# Telemetry_AnalogSensors_PTC08_Shifter.net
KiCad netlist of a schematic drawn in Altium Designer
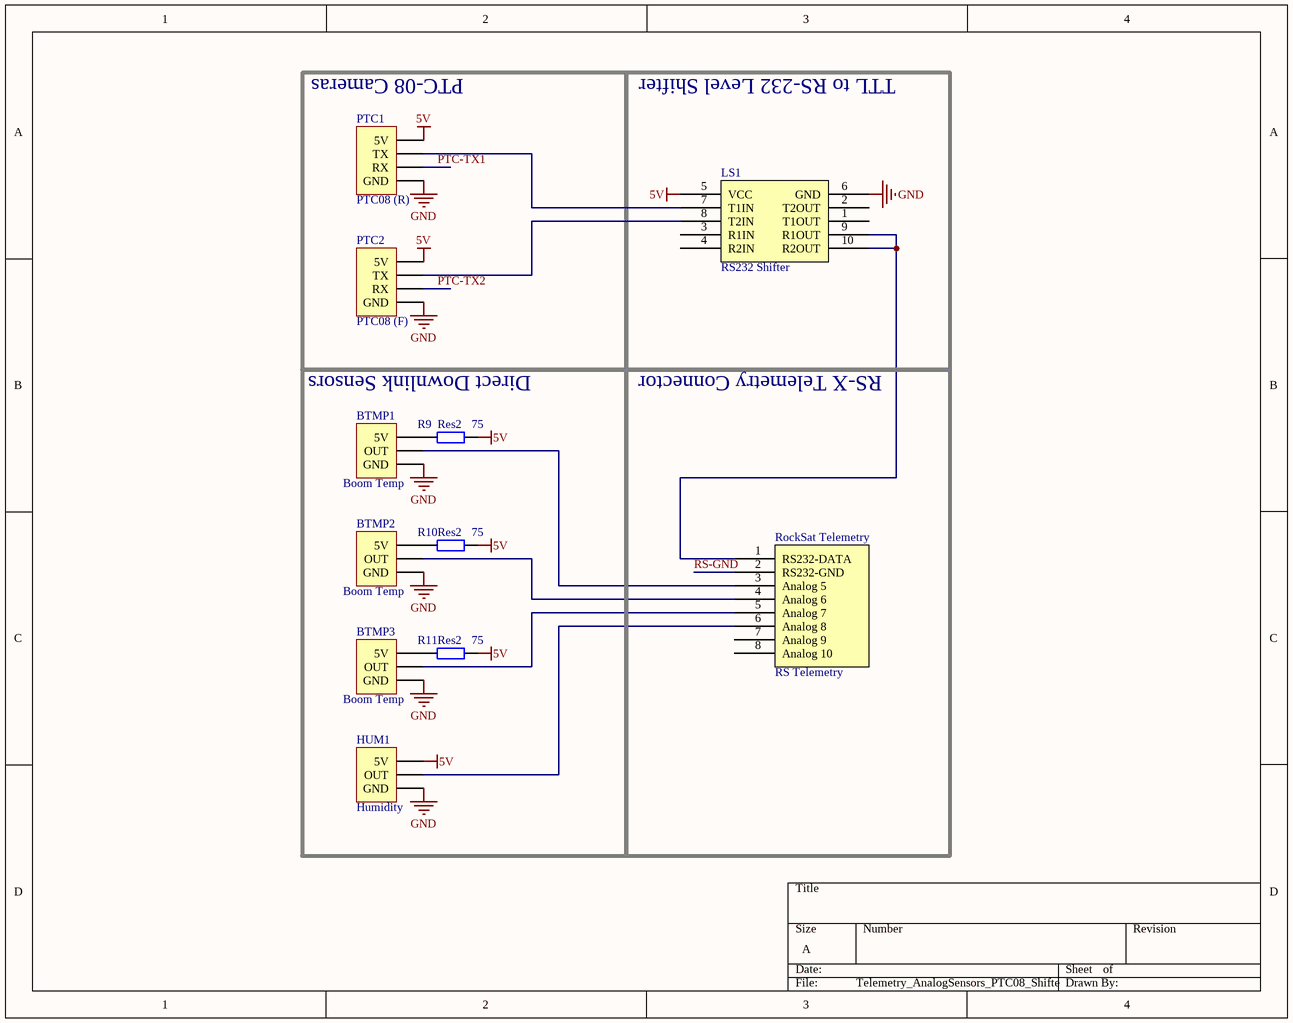
[diagram p0: Telemetry_AnalogSensors_PTC08_Shifter.SchDoc]

(export (version "E")
  (design (tool "Eeschema 10.0.6"))
  (components
    (comp (ref "BTMP1")
      (value "Boom Temp")
      (footprint "HDR1X3")
      (description "Header, 3-Pin")
      (fields (field (name "PUBLISHER") "Altium Limited"))
      (libsource (lib "Miscellaneous Connectors") (part "Header 3"))
    )
    (comp (ref "BTMP2")
      (value "Boom Temp")
      (footprint "HDR1X3")
      (description "Header, 3-Pin")
      (fields (field (name "PUBLISHER") "Altium Limited"))
      (libsource (lib "Miscellaneous Connectors") (part "Header 3"))
    )
    (comp (ref "BTMP3")
      (value "Boom Temp")
      (footprint "HDR1X3")
      (description "Header, 3-Pin")
      (fields (field (name "PUBLISHER") "Altium Limited"))
      (libsource (lib "Miscellaneous Connectors") (part "Header 3"))
    )
    (comp (ref "HUM1")
      (value "Humidity")
      (footprint "HDR1X3")
      (description "Header, 3-Pin")
      (fields (field (name "PUBLISHER") "Altium Limited"))
      (libsource (lib "Miscellaneous Connectors") (part "Header 3"))
    )
    (comp (ref "LS1") (value "RS232 Shifter") (libsource (lib "MAX3232") (part "Component_1")))
    (comp (ref "PTC1")
      (value "PTC08 (R)")
      (footprint "HDR1X4")
      (description "Header, 4-Pin")
      (fields (field (name "PUBLISHER") "Altium Limited"))
      (libsource (lib "Miscellaneous Connectors") (part "Header 4"))
    )
    (comp (ref "PTC2")
      (value "PTC08 (F)")
      (footprint "HDR1X4")
      (description "Header, 4-Pin")
      (fields (field (name "PUBLISHER") "Altium Limited"))
      (libsource (lib "Miscellaneous Connectors") (part "Header 4"))
    )
    (comp (ref "R9")
      (value "Res2")
      (footprint "AXIAL-0.4")
      (description "Resistor")
      (fields (field (name "ALTIUM_VALUE") "75") (field (name "PUBLISHER") "Altium Limited"))
      (libsource (lib "Miscellaneous Devices") (part "Res2"))
    )
    (comp (ref "R10")
      (value "Res2")
      (footprint "AXIAL-0.4")
      (description "Resistor")
      (fields (field (name "ALTIUM_VALUE") "75") (field (name "PUBLISHER") "Altium Limited"))
      (libsource (lib "Miscellaneous Devices") (part "Res2"))
    )
    (comp (ref "R11")
      (value "Res2")
      (footprint "AXIAL-0.4")
      (description "Resistor")
      (fields (field (name "ALTIUM_VALUE") "75") (field (name "PUBLISHER") "Altium Limited"))
      (libsource (lib "Miscellaneous Devices") (part "Res2"))
    )
    (comp (ref "RockSat Telemetry")
      (value "RS Telemetry")
      (libsource (lib "RSX_Telemetry") (part "Component_1"))
    )
  )
  (nets
    (net (code "1") (name "/PTC-TX1") (class "Default")
      (node (ref "PTC1") (pin "3") (pinfunction "RX_3") (pintype "passive"))
    )
    (net (code "2") (name "/PTC-TX2") (class "Default")
      (node (ref "PTC2") (pin "3") (pinfunction "RX_3") (pintype "passive"))
    )
    (net (code "3") (name "/RS-GND") (class "Default")
      (node (ref "RockSat Telemetry") (pin "2") (pinfunction "RS232-GND_2") (pintype "passive"))
    )
    (net (code "4") (name "5V") (class "Default")
      (node (ref "HUM1") (pin "1") (pinfunction "5V_1") (pintype "passive"))
      (node (ref "LS1") (pin "5") (pinfunction "VCC_5") (pintype "passive"))
      (node (ref "PTC1") (pin "1") (pinfunction "5V_1") (pintype "passive"))
      (node (ref "PTC2") (pin "1") (pinfunction "5V_1") (pintype "passive"))
      (node (ref "R10") (pin "1") (pinfunction "1_1") (pintype "passive"))
      (node (ref "R11") (pin "1") (pinfunction "1_1") (pintype "passive"))
      (node (ref "R9") (pin "1") (pinfunction "1_1") (pintype "passive"))
    )
    (net (code "5") (name "GND") (class "Default")
      (node (ref "BTMP1") (pin "3") (pinfunction "GND_3") (pintype "passive"))
      (node (ref "BTMP2") (pin "3") (pinfunction "GND_3") (pintype "passive"))
      (node (ref "BTMP3") (pin "3") (pinfunction "GND_3") (pintype "passive"))
      (node (ref "HUM1") (pin "3") (pinfunction "GND_3") (pintype "passive"))
      (node (ref "LS1") (pin "6") (pinfunction "GND_6") (pintype "passive"))
      (node (ref "PTC1") (pin "4") (pinfunction "GND_4") (pintype "passive"))
      (node (ref "PTC2") (pin "4") (pinfunction "GND_4") (pintype "passive"))
    )
    (net (code "6") (name "Net-(BTMP1-5V)") (class "Default")
      (node (ref "BTMP1") (pin "1") (pinfunction "5V_1") (pintype "passive"))
      (node (ref "R9") (pin "2") (pinfunction "2_2") (pintype "passive"))
    )
    (net (code "7") (name "Net-(BTMP1-OUT)") (class "Default")
      (node (ref "BTMP1") (pin "2") (pinfunction "OUT_2") (pintype "passive"))
      (node (ref "RockSat Telemetry") (pin "3") (pinfunction "Analog_5_3") (pintype "passive"))
    )
    (net (code "8") (name "Net-(BTMP2-5V)") (class "Default")
      (node (ref "BTMP2") (pin "1") (pinfunction "5V_1") (pintype "passive"))
      (node (ref "R10") (pin "2") (pinfunction "2_2") (pintype "passive"))
    )
    (net (code "9") (name "Net-(BTMP2-OUT)") (class "Default")
      (node (ref "BTMP2") (pin "2") (pinfunction "OUT_2") (pintype "passive"))
      (node (ref "RockSat Telemetry") (pin "4") (pinfunction "Analog_6_4") (pintype "passive"))
    )
    (net (code "10") (name "Net-(BTMP3-5V)") (class "Default")
      (node (ref "BTMP3") (pin "1") (pinfunction "5V_1") (pintype "passive"))
      (node (ref "R11") (pin "2") (pinfunction "2_2") (pintype "passive"))
    )
    (net (code "11") (name "Net-(BTMP3-OUT)") (class "Default")
      (node (ref "BTMP3") (pin "2") (pinfunction "OUT_2") (pintype "passive"))
      (node (ref "RockSat Telemetry") (pin "5") (pinfunction "Analog_7_5") (pintype "passive"))
    )
    (net (code "12") (name "Net-(HUM1-OUT)") (class "Default")
      (node (ref "HUM1") (pin "2") (pinfunction "OUT_2") (pintype "passive"))
      (node (ref "RockSat Telemetry") (pin "6") (pinfunction "Analog_8_6") (pintype "passive"))
    )
    (net (code "13") (name "Net-(LS1-R1OUT)") (class "Default")
      (node (ref "LS1") (pin "10") (pinfunction "R2OUT_10") (pintype "passive"))
      (node (ref "LS1") (pin "9") (pinfunction "R1OUT_9") (pintype "passive"))
      (node (ref "RockSat Telemetry") (pin "1") (pinfunction "RS232-DATA_1") (pintype "passive"))
    )
    (net (code "14") (name "Net-(LS1-T1IN)") (class "Default")
      (node (ref "LS1") (pin "7") (pinfunction "T1IN_7") (pintype "passive"))
      (node (ref "PTC1") (pin "2") (pinfunction "TX_2") (pintype "passive"))
    )
    (net (code "15") (name "Net-(LS1-T2IN)") (class "Default")
      (node (ref "LS1") (pin "8") (pinfunction "T2IN_8") (pintype "passive"))
      (node (ref "PTC2") (pin "2") (pinfunction "TX_2") (pintype "passive"))
    )
    (net (code "16") (name "unconnected-(LS1-R1IN-Pad3)") (class "Default")
      (node (ref "LS1") (pin "3") (pinfunction "R1IN_3") (pintype "passive"))
    )
    (net (code "17") (name "unconnected-(LS1-R2IN-Pad4)") (class "Default")
      (node (ref "LS1") (pin "4") (pinfunction "R2IN_4") (pintype "passive"))
    )
    (net (code "18") (name "unconnected-(LS1-T1OUT-Pad1)") (class "Default")
      (node (ref "LS1") (pin "1") (pinfunction "T1OUT_1") (pintype "passive"))
    )
    (net (code "19") (name "unconnected-(LS1-T2OUT-Pad2)") (class "Default")
      (node (ref "LS1") (pin "2") (pinfunction "T2OUT_2") (pintype "passive"))
    )
    (net (code "20") (name "unconnected-(RockSat Telemetry-Analog_9-Pad7)") (class "Default")
      (node (ref "RockSat Telemetry") (pin "7") (pinfunction "Analog_9_7") (pintype "passive"))
    )
    (net (code "21") (name "unconnected-(RockSat Telemetry-Analog_10-Pad8)") (class "Default")
      (node (ref "RockSat Telemetry") (pin "8") (pinfunction "Analog_10_8") (pintype "passive"))
    )
  )
)
